# v1.net
KiCad netlist of a schematic drawn in EAGLE
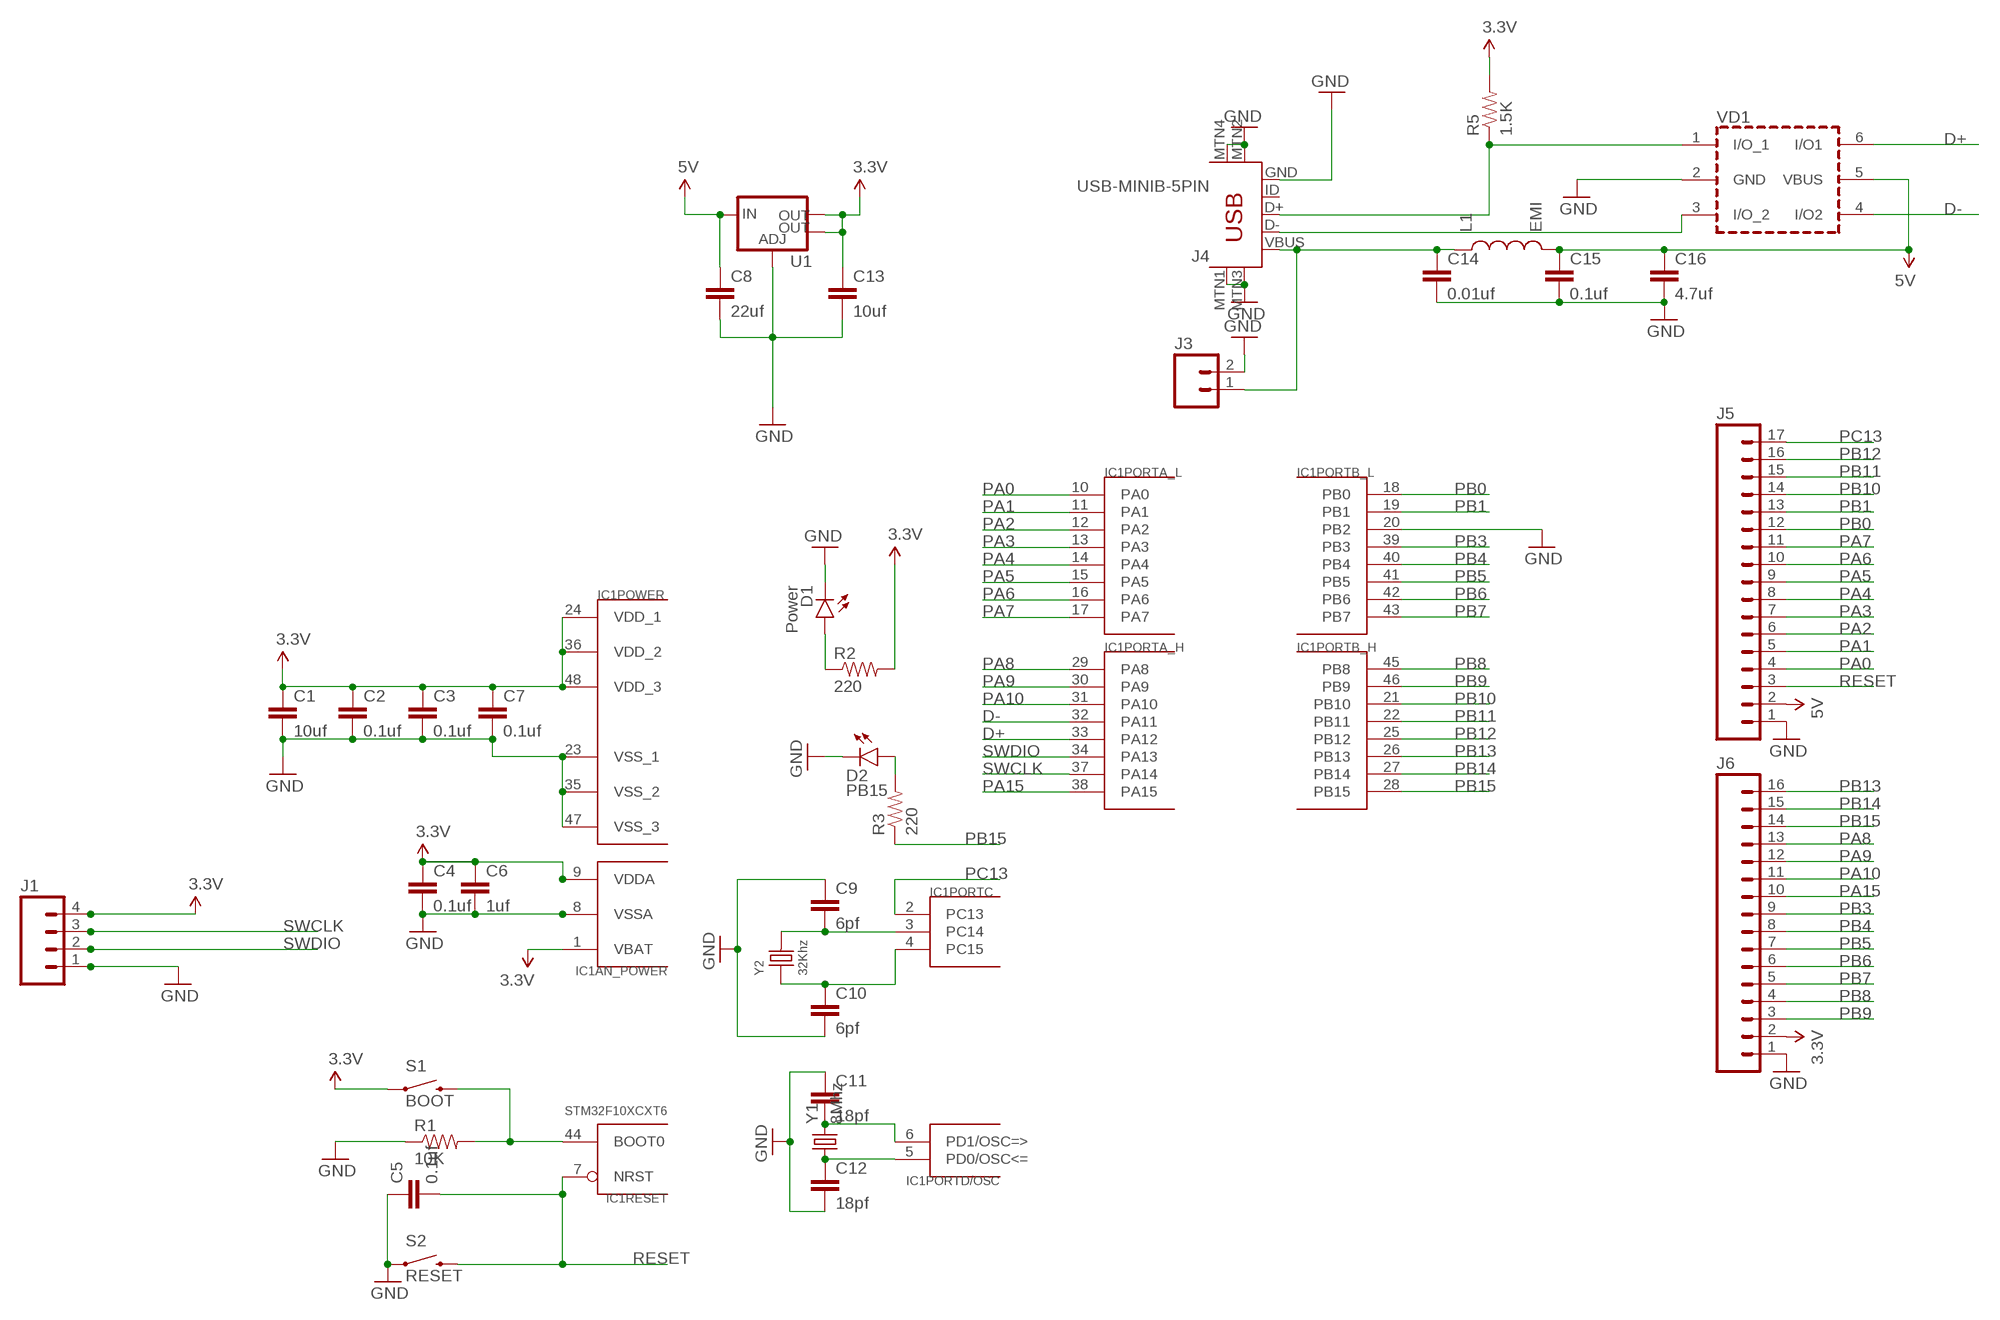
[diagram p0: schematic, sheet 1]

(export (version "E")
  (design (tool "Eeschema 10.0.6"))
  (components
    (comp (ref "C1")
      (value "10uf")
      (footprint "eagle-import:0805")
      (libsource (lib "eagle-import") (part "CAP0805"))
    )
    (comp (ref "C2")
      (value "0.1uf")
      (footprint "eagle-import:0805")
      (libsource (lib "eagle-import") (part "CAP0805"))
    )
    (comp (ref "C3")
      (value "0.1uf")
      (footprint "eagle-import:0805")
      (libsource (lib "eagle-import") (part "CAP0805"))
    )
    (comp (ref "C4")
      (value "0.1uf")
      (footprint "eagle-import:0805")
      (libsource (lib "eagle-import") (part "CAP0805"))
    )
    (comp (ref "C5")
      (value "0.1uf")
      (footprint "eagle-import:0805")
      (libsource (lib "eagle-import") (part "CAP0805"))
    )
    (comp (ref "C6")
      (value "1uf")
      (footprint "eagle-import:0805")
      (libsource (lib "eagle-import") (part "CAP0805"))
    )
    (comp (ref "C7")
      (value "0.1uf")
      (footprint "eagle-import:0805")
      (libsource (lib "eagle-import") (part "CAP0805"))
    )
    (comp (ref "C8")
      (value "22uf")
      (footprint "eagle-import:0805")
      (libsource (lib "eagle-import") (part "CAP0805"))
    )
    (comp (ref "C9")
      (value "6pf")
      (footprint "eagle-import:0805")
      (libsource (lib "eagle-import") (part "CAP0805"))
    )
    (comp (ref "C10")
      (value "6pf")
      (footprint "eagle-import:0805")
      (libsource (lib "eagle-import") (part "CAP0805"))
    )
    (comp (ref "C11")
      (value "18pf")
      (footprint "eagle-import:0805")
      (libsource (lib "eagle-import") (part "CAP0805"))
    )
    (comp (ref "C12")
      (value "18pf")
      (footprint "eagle-import:0805")
      (libsource (lib "eagle-import") (part "CAP0805"))
    )
    (comp (ref "C13")
      (value "10uf")
      (footprint "eagle-import:0805")
      (libsource (lib "eagle-import") (part "CAP0805"))
    )
    (comp (ref "C14")
      (value "0.01uf")
      (footprint "eagle-import:0805")
      (libsource (lib "eagle-import") (part "CAP0805"))
    )
    (comp (ref "C15")
      (value "0.1uf")
      (footprint "eagle-import:0805")
      (libsource (lib "eagle-import") (part "CAP0805"))
    )
    (comp (ref "C16")
      (value "4.7uf")
      (footprint "eagle-import:0805")
      (libsource (lib "eagle-import") (part "CAP0805"))
    )
    (comp (ref "D1")
      (value "Power")
      (footprint "eagle-import:LED-1206")
      (libsource (lib "eagle-import") (part "LED1206"))
    )
    (comp (ref "D2")
      (value "PB15")
      (footprint "eagle-import:LED-1206")
      (libsource (lib "eagle-import") (part "LED1206"))
    )
    (comp (ref "IC1")
      (value "STM32F10XCXT6")
      (footprint "eagle-import:TQFP48")
      (libsource (lib "eagle-import") (part "STM32F10XCXT6"))
    )
    (comp (ref "J1")
      (value "M04NO_SILK_ALL_ROUND")
      (footprint "eagle-import:1X04_NO_SILK_ALL_ROUND")
      (libsource (lib "eagle-import") (part "M04NO_SILK_ALL_ROUND"))
    )
    (comp (ref "J3")
      (value "M021X02_NO_SILK")
      (footprint "eagle-import:1X02_NO_SILK")
      (libsource (lib "eagle-import") (part "M021X02_NO_SILK"))
    )
    (comp (ref "J4")
      (value "USB-MINIB-5PIN")
      (footprint "eagle-import:USB-MINIB")
      (libsource (lib "eagle-import") (part "USB-MINIB-5PIN"))
    )
    (comp (ref "J5")
      (value "M17NOSILK")
      (footprint "eagle-import:1X17_NO_SILK")
      (libsource (lib "eagle-import") (part "M17NOSILK"))
    )
    (comp (ref "J6")
      (value "M161X16_NO_SILK")
      (footprint "eagle-import:1X16_NO_SILK")
      (libsource (lib "eagle-import") (part "M161X16_NO_SILK"))
    )
    (comp (ref "L1")
      (value "EMI")
      (footprint "eagle-import:0805")
      (libsource (lib "eagle-import") (part "INDUCTOR0805"))
    )
    (comp (ref "R1")
      (value "10K")
      (footprint "eagle-import:0805")
      (libsource (lib "eagle-import") (part "RESISTOR0805-RES"))
    )
    (comp (ref "R2")
      (value "220")
      (footprint "eagle-import:0805")
      (libsource (lib "eagle-import") (part "RESISTOR0805-RES"))
    )
    (comp (ref "R3")
      (value "220")
      (footprint "eagle-import:0805")
      (libsource (lib "eagle-import") (part "RESISTOR0805-RES"))
    )
    (comp (ref "R5")
      (value "1.5K")
      (footprint "eagle-import:0805")
      (libsource (lib "eagle-import") (part "RESISTOR0805-RES"))
    )
    (comp (ref "S1")
      (value "BOOT")
      (footprint "eagle-import:TACTILE-SWITCH-1101NE")
      (libsource (lib "eagle-import") (part "SWITCH-MOMENTARY-2SMD-1101NE"))
    )
    (comp (ref "S2")
      (value "RESET")
      (footprint "eagle-import:TACTILE-SWITCH-1101NE")
      (libsource (lib "eagle-import") (part "SWITCH-MOMENTARY-2SMD-1101NE"))
    )
    (comp (ref "U1")
      (value "V_REG_LM1117SOT223")
      (footprint "eagle-import:SOT223")
      (libsource (lib "eagle-import") (part "V_REG_LM1117SOT223"))
    )
    (comp (ref "VD1")
      (value "USBLC6-2SC6")
      (footprint "eagle-import:SOT-23-6L")
      (libsource (lib "eagle-import") (part "USBLC6-2SC6"))
    )
    (comp (ref "Y1")
      (value "8Mhz")
      (footprint "eagle-import:CRYSTAL-SMD-5X3")
      (libsource (lib "eagle-import") (part "CRYSTALCRYSTAL-SMD-5X3-16MHZ"))
    )
    (comp (ref "Y2")
      (value "32Khz")
      (footprint "eagle-import:X2-SMD-3.2X1.5X0.55MM")
      (libsource (lib "eagle-import") (part "CRYSTAL-3215"))
    )
  )
  (nets
    (net (code "1") (name "/D+") (class "Default")
      (node (ref "IC1") (pin "33") (pinfunction "PA12_33") (pintype "bidirectional"))
      (node (ref "VD1") (pin "6") (pinfunction "I/O1_6") (pintype "bidirectional"))
    )
    (net (code "2") (name "/D-") (class "Default")
      (node (ref "IC1") (pin "32") (pinfunction "PA11_32") (pintype "bidirectional"))
      (node (ref "VD1") (pin "4") (pinfunction "I/O2_4") (pintype "bidirectional"))
    )
    (net (code "3") (name "/PA0") (class "Default")
      (node (ref "IC1") (pin "10") (pinfunction "PA0_10") (pintype "bidirectional"))
      (node (ref "J5") (pin "4") (pinfunction "4_4") (pintype "passive"))
    )
    (net (code "4") (name "/PA1") (class "Default")
      (node (ref "IC1") (pin "11") (pinfunction "PA1_11") (pintype "bidirectional"))
      (node (ref "J5") (pin "5") (pinfunction "5_5") (pintype "passive"))
    )
    (net (code "5") (name "/PA2") (class "Default")
      (node (ref "IC1") (pin "12") (pinfunction "PA2_12") (pintype "bidirectional"))
      (node (ref "J5") (pin "6") (pinfunction "6_6") (pintype "passive"))
    )
    (net (code "6") (name "/PA3") (class "Default")
      (node (ref "IC1") (pin "13") (pinfunction "PA3_13") (pintype "bidirectional"))
      (node (ref "J5") (pin "7") (pinfunction "7_7") (pintype "passive"))
    )
    (net (code "7") (name "/PA4") (class "Default")
      (node (ref "IC1") (pin "14") (pinfunction "PA4_14") (pintype "bidirectional"))
      (node (ref "J5") (pin "8") (pinfunction "8_8") (pintype "passive"))
    )
    (net (code "8") (name "/PA5") (class "Default")
      (node (ref "IC1") (pin "15") (pinfunction "PA5_15") (pintype "bidirectional"))
      (node (ref "J5") (pin "9") (pinfunction "9_9") (pintype "passive"))
    )
    (net (code "9") (name "/PA6") (class "Default")
      (node (ref "IC1") (pin "16") (pinfunction "PA6_16") (pintype "bidirectional"))
      (node (ref "J5") (pin "10") (pinfunction "10_10") (pintype "passive"))
    )
    (net (code "10") (name "/PA7") (class "Default")
      (node (ref "IC1") (pin "17") (pinfunction "PA7_17") (pintype "bidirectional"))
      (node (ref "J5") (pin "11") (pinfunction "11_11") (pintype "passive"))
    )
    (net (code "11") (name "/PA8") (class "Default")
      (node (ref "IC1") (pin "29") (pinfunction "PA8_29") (pintype "bidirectional"))
      (node (ref "J6") (pin "13") (pinfunction "13_13") (pintype "passive"))
    )
    (net (code "12") (name "/PA9") (class "Default")
      (node (ref "IC1") (pin "30") (pinfunction "PA9_30") (pintype "bidirectional"))
      (node (ref "J6") (pin "12") (pinfunction "12_12") (pintype "passive"))
    )
    (net (code "13") (name "/PA10") (class "Default")
      (node (ref "IC1") (pin "31") (pinfunction "PA10_31") (pintype "bidirectional"))
      (node (ref "J6") (pin "11") (pinfunction "11_11") (pintype "passive"))
    )
    (net (code "14") (name "/PA15") (class "Default")
      (node (ref "IC1") (pin "38") (pinfunction "PA15_38") (pintype "bidirectional"))
      (node (ref "J6") (pin "10") (pinfunction "10_10") (pintype "passive"))
    )
    (net (code "15") (name "/PB0") (class "Default")
      (node (ref "IC1") (pin "18") (pinfunction "PB0_18") (pintype "bidirectional"))
      (node (ref "J5") (pin "12") (pinfunction "12_12") (pintype "passive"))
    )
    (net (code "16") (name "/PB1") (class "Default")
      (node (ref "IC1") (pin "19") (pinfunction "PB1_19") (pintype "bidirectional"))
      (node (ref "J5") (pin "13") (pinfunction "13_13") (pintype "passive"))
    )
    (net (code "17") (name "/PB3") (class "Default")
      (node (ref "IC1") (pin "39") (pinfunction "PB3_39") (pintype "bidirectional"))
      (node (ref "J6") (pin "9") (pinfunction "9_9") (pintype "passive"))
    )
    (net (code "18") (name "/PB4") (class "Default")
      (node (ref "IC1") (pin "40") (pinfunction "PB4_40") (pintype "bidirectional"))
      (node (ref "J6") (pin "8") (pinfunction "8_8") (pintype "passive"))
    )
    (net (code "19") (name "/PB5") (class "Default")
      (node (ref "IC1") (pin "41") (pinfunction "PB5_41") (pintype "bidirectional"))
      (node (ref "J6") (pin "7") (pinfunction "7_7") (pintype "passive"))
    )
    (net (code "20") (name "/PB6") (class "Default")
      (node (ref "IC1") (pin "42") (pinfunction "PB6_42") (pintype "bidirectional"))
      (node (ref "J6") (pin "6") (pinfunction "6_6") (pintype "passive"))
    )
    (net (code "21") (name "/PB7") (class "Default")
      (node (ref "IC1") (pin "43") (pinfunction "PB7_43") (pintype "bidirectional"))
      (node (ref "J6") (pin "5") (pinfunction "5_5") (pintype "passive"))
    )
    (net (code "22") (name "/PB8") (class "Default")
      (node (ref "IC1") (pin "45") (pinfunction "PB8_45") (pintype "bidirectional"))
      (node (ref "J6") (pin "4") (pinfunction "4_4") (pintype "passive"))
    )
    (net (code "23") (name "/PB9") (class "Default")
      (node (ref "IC1") (pin "46") (pinfunction "PB9_46") (pintype "bidirectional"))
      (node (ref "J6") (pin "3") (pinfunction "3_3") (pintype "passive"))
    )
    (net (code "24") (name "/PB10") (class "Default")
      (node (ref "IC1") (pin "21") (pinfunction "PB10_21") (pintype "bidirectional"))
      (node (ref "J5") (pin "14") (pinfunction "14_14") (pintype "passive"))
    )
    (net (code "25") (name "/PB11") (class "Default")
      (node (ref "IC1") (pin "22") (pinfunction "PB11_22") (pintype "bidirectional"))
      (node (ref "J5") (pin "15") (pinfunction "15_15") (pintype "passive"))
    )
    (net (code "26") (name "/PB12") (class "Default")
      (node (ref "IC1") (pin "25") (pinfunction "PB12_25") (pintype "bidirectional"))
      (node (ref "J5") (pin "16") (pinfunction "16_16") (pintype "passive"))
    )
    (net (code "27") (name "/PB13") (class "Default")
      (node (ref "IC1") (pin "26") (pinfunction "PB13_26") (pintype "bidirectional"))
      (node (ref "J6") (pin "16") (pinfunction "16_16") (pintype "passive"))
    )
    (net (code "28") (name "/PB14") (class "Default")
      (node (ref "IC1") (pin "27") (pinfunction "PB14_27") (pintype "bidirectional"))
      (node (ref "J6") (pin "15") (pinfunction "15_15") (pintype "passive"))
    )
    (net (code "29") (name "/PB15") (class "Default")
      (node (ref "IC1") (pin "28") (pinfunction "PB15_28") (pintype "bidirectional"))
      (node (ref "J6") (pin "14") (pinfunction "14_14") (pintype "passive"))
      (node (ref "R3") (pin "1") (pinfunction "1_1") (pintype "passive"))
    )
    (net (code "30") (name "/PC13") (class "Default")
      (node (ref "IC1") (pin "2") (pinfunction "PC13_2") (pintype "bidirectional"))
      (node (ref "J5") (pin "17") (pinfunction "17_17") (pintype "passive"))
    )
    (net (code "31") (name "/RESET") (class "Default")
      (node (ref "C5") (pin "2") (pinfunction "2_2") (pintype "passive"))
      (node (ref "IC1") (pin "7") (pinfunction "NRST_7") (pintype "input"))
      (node (ref "J5") (pin "3") (pinfunction "3_3") (pintype "passive"))
      (node (ref "S2") (pin "2") (pinfunction "2_2") (pintype "passive"))
    )
    (net (code "32") (name "/SWCLK") (class "Default")
      (node (ref "IC1") (pin "37") (pinfunction "PA14_37") (pintype "bidirectional"))
      (node (ref "J1") (pin "3") (pinfunction "3_3") (pintype "passive"))
    )
    (net (code "33") (name "/SWDIO") (class "Default")
      (node (ref "IC1") (pin "34") (pinfunction "PA13_34") (pintype "bidirectional"))
      (node (ref "J1") (pin "2") (pinfunction "2_2") (pintype "passive"))
    )
    (net (code "34") (name "3.3V") (class "Default")
      (node (ref "C1") (pin "1") (pinfunction "1_1") (pintype "passive"))
      (node (ref "C13") (pin "1") (pinfunction "1_1") (pintype "passive"))
      (node (ref "C2") (pin "1") (pinfunction "1_1") (pintype "passive"))
      (node (ref "C3") (pin "1") (pinfunction "1_1") (pintype "passive"))
      (node (ref "C4") (pin "1") (pinfunction "1_1") (pintype "passive"))
      (node (ref "C6") (pin "1") (pinfunction "1_1") (pintype "passive"))
      (node (ref "C7") (pin "1") (pinfunction "1_1") (pintype "passive"))
      (node (ref "IC1") (pin "1") (pinfunction "VBAT_1") (pintype "power_in"))
      (node (ref "IC1") (pin "24") (pinfunction "VDD_1_24") (pintype "power_in"))
      (node (ref "IC1") (pin "36") (pinfunction "VDD_2_36") (pintype "power_in"))
      (node (ref "IC1") (pin "48") (pinfunction "VDD_3_48") (pintype "power_in"))
      (node (ref "IC1") (pin "9") (pinfunction "VDDA_9") (pintype "power_in"))
      (node (ref "J1") (pin "4") (pinfunction "4_4") (pintype "passive"))
      (node (ref "J6") (pin "2") (pinfunction "2_2") (pintype "passive"))
      (node (ref "R2") (pin "2") (pinfunction "2_2") (pintype "passive"))
      (node (ref "R5") (pin "2") (pinfunction "2_2") (pintype "passive"))
      (node (ref "S1") (pin "1") (pinfunction "1_1") (pintype "passive"))
      (node (ref "U1") (pin "2") (pinfunction "OUT_2") (pintype "output"))
      (node (ref "U1") (pin "4") (pinfunction "OUT_4") (pintype "output"))
    )
    (net (code "35") (name "5V") (class "Default")
      (node (ref "C15") (pin "1") (pinfunction "1_1") (pintype "passive"))
      (node (ref "C16") (pin "1") (pinfunction "1_1") (pintype "passive"))
      (node (ref "C8") (pin "1") (pinfunction "1_1") (pintype "passive"))
      (node (ref "J5") (pin "2") (pinfunction "2_2") (pintype "passive"))
      (node (ref "L1") (pin "2") (pinfunction "2_2") (pintype "passive"))
      (node (ref "U1") (pin "3") (pinfunction "IN_3") (pintype "input"))
      (node (ref "VD1") (pin "5") (pinfunction "VBUS_5") (pintype "bidirectional"))
    )
    (net (code "36") (name "GND") (class "Default")
      (node (ref "C1") (pin "2") (pinfunction "2_2") (pintype "passive"))
      (node (ref "C10") (pin "2") (pinfunction "2_2") (pintype "passive"))
      (node (ref "C11") (pin "1") (pinfunction "1_1") (pintype "passive"))
      (node (ref "C12") (pin "2") (pinfunction "2_2") (pintype "passive"))
      (node (ref "C13") (pin "2") (pinfunction "2_2") (pintype "passive"))
      (node (ref "C14") (pin "2") (pinfunction "2_2") (pintype "passive"))
      (node (ref "C15") (pin "2") (pinfunction "2_2") (pintype "passive"))
      (node (ref "C16") (pin "2") (pinfunction "2_2") (pintype "passive"))
      (node (ref "C2") (pin "2") (pinfunction "2_2") (pintype "passive"))
      (node (ref "C3") (pin "2") (pinfunction "2_2") (pintype "passive"))
      (node (ref "C4") (pin "2") (pinfunction "2_2") (pintype "passive"))
      (node (ref "C5") (pin "1") (pinfunction "1_1") (pintype "passive"))
      (node (ref "C6") (pin "2") (pinfunction "2_2") (pintype "passive"))
      (node (ref "C7") (pin "2") (pinfunction "2_2") (pintype "passive"))
      (node (ref "C8") (pin "2") (pinfunction "2_2") (pintype "passive"))
      (node (ref "C9") (pin "1") (pinfunction "1_1") (pintype "passive"))
      (node (ref "D1") (pin "C") (pinfunction "C_C") (pintype "passive"))
      (node (ref "D2") (pin "C") (pinfunction "C_C") (pintype "passive"))
      (node (ref "IC1") (pin "20") (pinfunction "PB2_20") (pintype "bidirectional"))
      (node (ref "IC1") (pin "23") (pinfunction "VSS_1_23") (pintype "power_in"))
      (node (ref "IC1") (pin "35") (pinfunction "VSS_2_35") (pintype "power_in"))
      (node (ref "IC1") (pin "47") (pinfunction "VSS_3_47") (pintype "power_in"))
      (node (ref "IC1") (pin "8") (pinfunction "VSSA_8") (pintype "power_in"))
      (node (ref "J1") (pin "1") (pinfunction "1_1") (pintype "passive"))
      (node (ref "J3") (pin "2") (pinfunction "2_2") (pintype "passive"))
      (node (ref "J4") (pin "GND") (pinfunction "GND_GND") (pintype "bidirectional"))
      (node (ref "J4") (pin "MTN1") (pinfunction "MTN2_MTN1") (pintype "bidirectional"))
      (node (ref "J4") (pin "MTN2") (pinfunction "MTN3_MTN2") (pintype "bidirectional"))
      (node (ref "J4") (pin "MTN3") (pinfunction "MTN1_MTN3") (pintype "bidirectional"))
      (node (ref "J4") (pin "MTN4") (pinfunction "MTN4_MTN4") (pintype "bidirectional"))
      (node (ref "J5") (pin "1") (pinfunction "1_1") (pintype "passive"))
      (node (ref "J6") (pin "1") (pinfunction "1_1") (pintype "passive"))
      (node (ref "R1") (pin "1") (pinfunction "1_1") (pintype "passive"))
      (node (ref "S2") (pin "1") (pinfunction "1_1") (pintype "passive"))
      (node (ref "U1") (pin "1") (pinfunction "ADJ_1") (pintype "input"))
      (node (ref "VD1") (pin "2") (pinfunction "GND_2") (pintype "bidirectional"))
    )
    (net (code "37") (name "Net-(C14-Pad1)") (class "Default")
      (node (ref "C14") (pin "1") (pinfunction "1_1") (pintype "passive"))
      (node (ref "J3") (pin "1") (pinfunction "1_1") (pintype "passive"))
      (node (ref "J4") (pin "VBUS") (pinfunction "VBUS_VBUS") (pintype "bidirectional"))
      (node (ref "L1") (pin "1") (pinfunction "1_1") (pintype "passive"))
    )
    (net (code "38") (name "Net-(D1-PadA)") (class "Default")
      (node (ref "D1") (pin "A") (pinfunction "A_A") (pintype "passive"))
      (node (ref "R2") (pin "1") (pinfunction "1_1") (pintype "passive"))
    )
    (net (code "39") (name "Net-(D2-PadA)") (class "Default")
      (node (ref "D2") (pin "A") (pinfunction "A_A") (pintype "passive"))
      (node (ref "R3") (pin "2") (pinfunction "2_2") (pintype "passive"))
    )
    (net (code "40") (name "Net-(IC1F-PC14)") (class "Default")
      (node (ref "C9") (pin "2") (pinfunction "2_2") (pintype "passive"))
      (node (ref "IC1") (pin "3") (pinfunction "PC14_3") (pintype "bidirectional"))
      (node (ref "Y2") (pin "2") (pinfunction "2_2") (pintype "passive"))
    )
    (net (code "41") (name "Net-(IC1F-PC15)") (class "Default")
      (node (ref "C10") (pin "1") (pinfunction "1_1") (pintype "passive"))
      (node (ref "IC1") (pin "4") (pinfunction "PC15_4") (pintype "bidirectional"))
      (node (ref "Y2") (pin "1") (pinfunction "1_1") (pintype "passive"))
    )
    (net (code "42") (name "Net-(IC1G-PD0{slash}OSC<=)") (class "Default")
      (node (ref "C12") (pin "1") (pinfunction "1_1") (pintype "passive"))
      (node (ref "IC1") (pin "5") (pinfunction "PD0/OSC<=_5") (pintype "bidirectional"))
      (node (ref "Y1") (pin "1") (pinfunction "1_1") (pintype "passive"))
    )
    (net (code "43") (name "Net-(IC1G-PD1{slash}OSC=>)") (class "Default")
      (node (ref "C11") (pin "2") (pinfunction "2_2") (pintype "passive"))
      (node (ref "IC1") (pin "6") (pinfunction "PD1/OSC=>_6") (pintype "bidirectional"))
      (node (ref "Y1") (pin "3") (pinfunction "2_3") (pintype "passive"))
    )
    (net (code "44") (name "Net-(IC1I-BOOT0)") (class "Default")
      (node (ref "IC1") (pin "44") (pinfunction "BOOT0_44") (pintype "input"))
      (node (ref "R1") (pin "2") (pinfunction "2_2") (pintype "passive"))
      (node (ref "S1") (pin "2") (pinfunction "2_2") (pintype "passive"))
    )
    (net (code "45") (name "Net-(VD1-I{slash}O_1)") (class "Default")
      (node (ref "J4") (pin "D+") (pinfunction "D+_D+") (pintype "bidirectional"))
      (node (ref "R5") (pin "1") (pinfunction "1_1") (pintype "passive"))
      (node (ref "VD1") (pin "1") (pinfunction "I/O_1_1") (pintype "bidirectional"))
    )
    (net (code "46") (name "Net-(VD1-I{slash}O_2)") (class "Default")
      (node (ref "J4") (pin "D-") (pinfunction "D-_D-") (pintype "bidirectional"))
      (node (ref "VD1") (pin "3") (pinfunction "I/O_2_3") (pintype "bidirectional"))
    )
    (net (code "47") (name "unconnected-(J4-PadID)") (class "Default")
      (node (ref "J4") (pin "ID") (pinfunction "ID_ID") (pintype "bidirectional"))
    )
  )
)
